# source_eagle.net
KiCad netlist of a schematic drawn in EAGLE
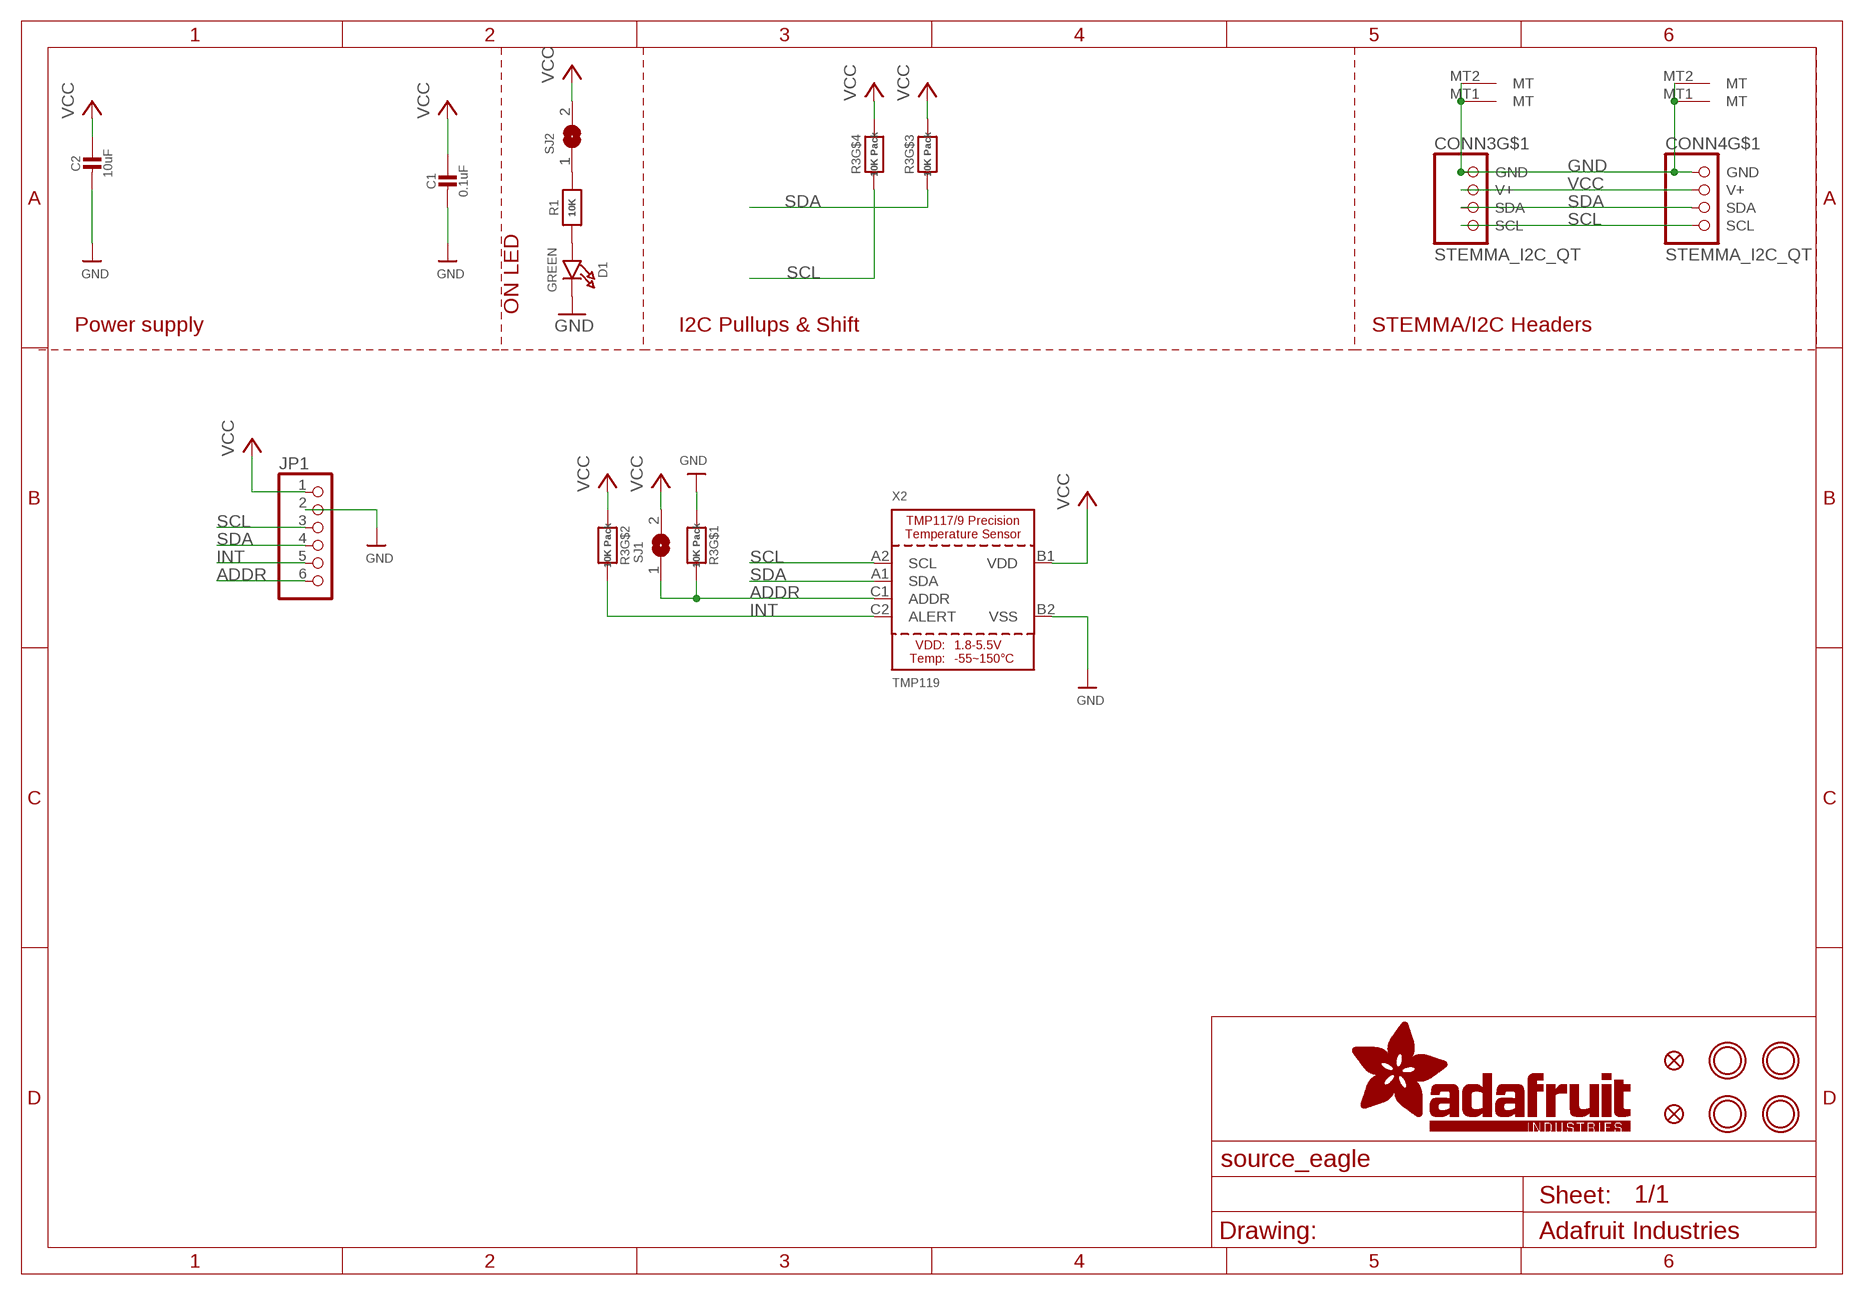
[diagram p0: schematic, sheet 1]

(export (version "E")
  (design (tool "Eeschema 10.0.6"))
  (components
    (comp (ref "C1")
      (value "0.1uF")
      (footprint "eagle-import:0603-NO")
      (libsource (lib "eagle-import") (part "CAP_CERAMIC0603_NO"))
    )
    (comp (ref "C2")
      (value "10uF")
      (footprint "eagle-import:0805-NO")
      (libsource (lib "eagle-import") (part "CAP_CERAMIC0805-NOOUTLINE"))
    )
    (comp (ref "CONN3")
      (value "STEMMA_I2C_QT")
      (footprint "eagle-import:JST_SH4")
      (libsource (lib "eagle-import") (part "STEMMA_I2C_QT"))
    )
    (comp (ref "CONN4")
      (value "STEMMA_I2C_QT")
      (footprint "eagle-import:JST_SH4")
      (libsource (lib "eagle-import") (part "STEMMA_I2C_QT"))
    )
    (comp (ref "D1")
      (value "GREEN")
      (footprint "eagle-import:CHIPLED_0603_NOOUTLINE")
      (libsource (lib "eagle-import") (part "LED0603_NOOUTLINE"))
    )
    (comp (ref "FID3")
      (value "FIDUCIAL_0.5MM")
      (footprint "eagle-import:FIDUCIAL_0.5MM")
      (libsource (lib "eagle-import") (part "FIDUCIAL_0.5MM"))
    )
    (comp (ref "FID4")
      (value "FIDUCIAL_0.5MM")
      (footprint "eagle-import:FIDUCIAL_0.5MM")
      (libsource (lib "eagle-import") (part "FIDUCIAL_0.5MM"))
    )
    (comp (ref "JP1")
      (value "HEADER-1X670MIL")
      (footprint "eagle-import:1X06_ROUND_70")
      (libsource (lib "eagle-import") (part "HEADER-1X670MIL"))
    )
    (comp (ref "R1")
      (value "10K")
      (footprint "eagle-import:0603-NO")
      (libsource (lib "eagle-import") (part "RESISTOR_0603_NOOUT"))
    )
    (comp (ref "R3")
      (value "10K Pack")
      (footprint "eagle-import:RESPACK_4X0603")
      (libsource (lib "eagle-import") (part "RESISTOR_4PACK"))
    )
    (comp (ref "SJ1")
      (value "SOLDERJUMPER")
      (footprint "eagle-import:SOLDERJUMPER_ARROW_NOPASTE")
      (libsource (lib "eagle-import") (part "SOLDERJUMPER"))
    )
    (comp (ref "SJ2")
      (value "SOLDERJUMPERCLOSED")
      (footprint "eagle-import:SOLDERJUMPER_CLOSEDWIRE")
      (libsource (lib "eagle-import") (part "SOLDERJUMPERCLOSED"))
    )
    (comp (ref "U$1")
      (value "MOUNTINGHOLE2.5")
      (footprint "eagle-import:MOUNTINGHOLE_2.5_PLATED")
      (libsource (lib "eagle-import") (part "MOUNTINGHOLE2.5"))
    )
    (comp (ref "U$17")
      (value "MOUNTINGHOLE2.5")
      (footprint "eagle-import:MOUNTINGHOLE_2.5_PLATED")
      (libsource (lib "eagle-import") (part "MOUNTINGHOLE2.5"))
    )
    (comp (ref "U$19")
      (value "MOUNTINGHOLE2.5")
      (footprint "eagle-import:MOUNTINGHOLE_2.5_PLATED")
      (libsource (lib "eagle-import") (part "MOUNTINGHOLE2.5"))
    )
    (comp (ref "U$21")
      (value "MOUNTINGHOLE2.5")
      (footprint "eagle-import:MOUNTINGHOLE_2.5_PLATED")
      (libsource (lib "eagle-import") (part "MOUNTINGHOLE2.5"))
    )
    (comp (ref "X2")
      (value "TMP119")
      (footprint "eagle-import:DSBGA-9")
      (libsource (lib "eagle-import") (part "TMP119"))
    )
  )
  (nets
    (net (code "1") (name "/ADDR") (class "Default")
      (node (ref "JP1") (pin "6") (pinfunction "6_6") (pintype "passive"))
      (node (ref "R3") (pin "8") (pinfunction "2_8") (pintype "passive"))
      (node (ref "SJ1") (pin "1") (pinfunction "1_1") (pintype "passive"))
      (node (ref "X2") (pin "C1") (pinfunction "ADDR_C1") (pintype "input"))
    )
    (net (code "2") (name "/INT") (class "Default")
      (node (ref "JP1") (pin "5") (pinfunction "5_5") (pintype "passive"))
      (node (ref "R3") (pin "7") (pinfunction "2_7") (pintype "passive"))
      (node (ref "X2") (pin "C2") (pinfunction "ALERT_C2") (pintype "output"))
    )
    (net (code "3") (name "/SCL") (class "Default")
      (node (ref "CONN3") (pin "4") (pinfunction "SCL_4") (pintype "passive"))
      (node (ref "CONN4") (pin "4") (pinfunction "SCL_4") (pintype "passive"))
      (node (ref "JP1") (pin "3") (pinfunction "3_3") (pintype "passive"))
      (node (ref "R3") (pin "4") (pinfunction "1_4") (pintype "passive"))
      (node (ref "X2") (pin "A2") (pinfunction "SCL_A2") (pintype "bidirectional"))
    )
    (net (code "4") (name "/SDA") (class "Default")
      (node (ref "CONN3") (pin "3") (pinfunction "SDA_3") (pintype "passive"))
      (node (ref "CONN4") (pin "3") (pinfunction "SDA_3") (pintype "passive"))
      (node (ref "JP1") (pin "4") (pinfunction "4_4") (pintype "passive"))
      (node (ref "R3") (pin "3") (pinfunction "1_3") (pintype "passive"))
      (node (ref "X2") (pin "A1") (pinfunction "SDA_A1") (pintype "bidirectional"))
    )
    (net (code "5") (name "GND") (class "Default")
      (node (ref "C1") (pin "2") (pinfunction "2_2") (pintype "passive"))
      (node (ref "C2") (pin "2") (pinfunction "2_2") (pintype "passive"))
      (node (ref "CONN3") (pin "1") (pinfunction "GND_1") (pintype "passive"))
      (node (ref "CONN3") (pin "MT1") (pinfunction "MT_MT1") (pintype "bidirectional"))
      (node (ref "CONN3") (pin "MT2") (pinfunction "MT_MT2") (pintype "bidirectional"))
      (node (ref "CONN4") (pin "1") (pinfunction "GND_1") (pintype "passive"))
      (node (ref "CONN4") (pin "MT1") (pinfunction "MT_MT1") (pintype "bidirectional"))
      (node (ref "CONN4") (pin "MT2") (pinfunction "MT_MT2") (pintype "bidirectional"))
      (node (ref "D1") (pin "C") (pinfunction "C_C") (pintype "passive"))
      (node (ref "JP1") (pin "2") (pinfunction "2_2") (pintype "passive"))
      (node (ref "R3") (pin "1") (pinfunction "1_1") (pintype "passive"))
      (node (ref "X2") (pin "B2") (pinfunction "VSS_B2") (pintype "power_in"))
    )
    (net (code "6") (name "Net-(D1-PadA)") (class "Default")
      (node (ref "D1") (pin "A") (pinfunction "A_A") (pintype "passive"))
      (node (ref "R1") (pin "1") (pinfunction "1_1") (pintype "passive"))
    )
    (net (code "7") (name "Net-(R1-Pad2)") (class "Default")
      (node (ref "R1") (pin "2") (pinfunction "2_2") (pintype "passive"))
      (node (ref "SJ2") (pin "1") (pinfunction "1_1") (pintype "passive"))
    )
    (net (code "8") (name "VCC") (class "Default")
      (node (ref "C1") (pin "1") (pinfunction "1_1") (pintype "passive"))
      (node (ref "C2") (pin "1") (pinfunction "1_1") (pintype "passive"))
      (node (ref "CONN3") (pin "2") (pinfunction "V+_2") (pintype "passive"))
      (node (ref "CONN4") (pin "2") (pinfunction "V+_2") (pintype "passive"))
      (node (ref "JP1") (pin "1") (pinfunction "1_1") (pintype "passive"))
      (node (ref "R3") (pin "2") (pinfunction "1_2") (pintype "passive"))
      (node (ref "R3") (pin "5") (pinfunction "2_5") (pintype "passive"))
      (node (ref "R3") (pin "6") (pinfunction "2_6") (pintype "passive"))
      (node (ref "SJ1") (pin "2") (pinfunction "2_2") (pintype "passive"))
      (node (ref "SJ2") (pin "2") (pinfunction "2_2") (pintype "passive"))
      (node (ref "X2") (pin "B1") (pinfunction "VDD_B1") (pintype "power_in"))
    )
  )
)
